# servo.net
KiCad netlist of a schematic drawn in EAGLE
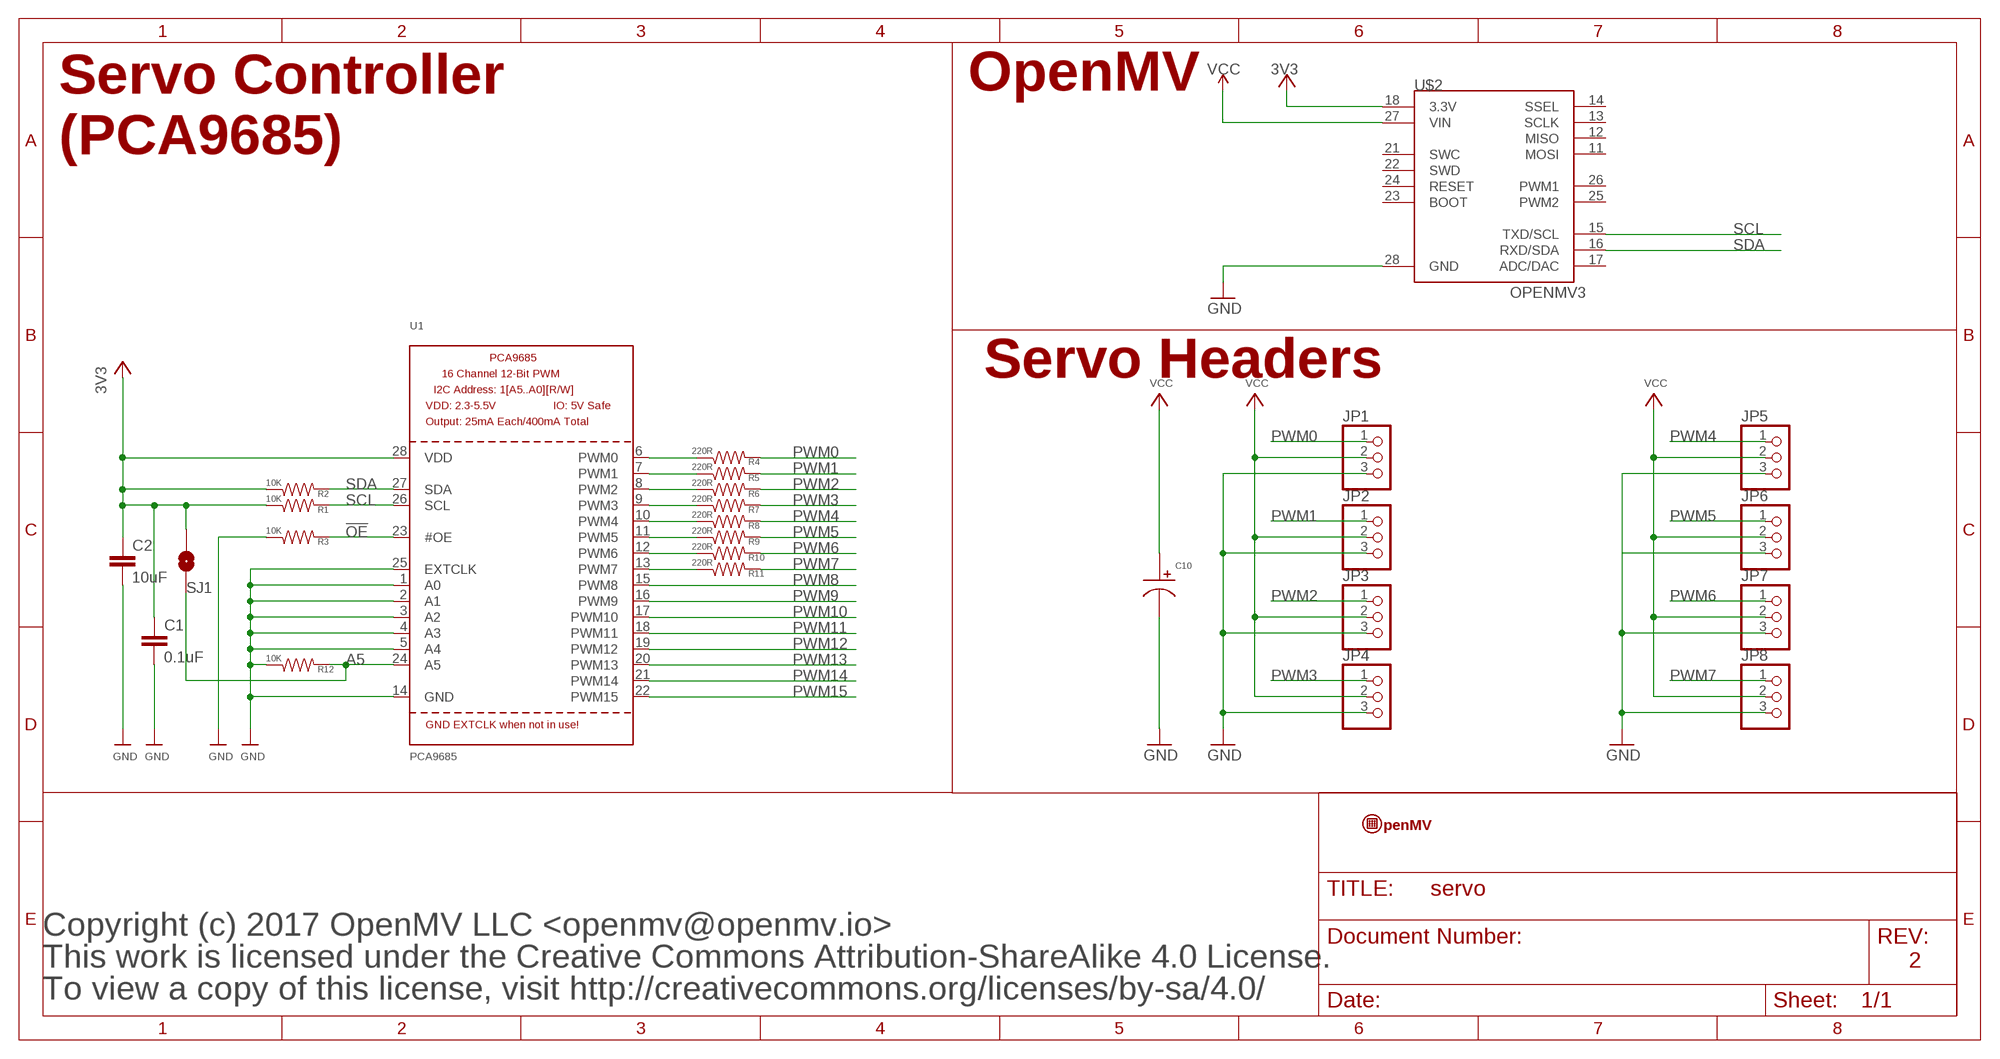
[diagram p0: schematic, sheet 1]

(export (version "E")
  (design (tool "Eeschema 10.0.6"))
  (components
    (comp (ref "C1")
      (value "0.1uF")
      (footprint "eagle-import:0603-CAP")
      (libsource (lib "eagle-import") (part "CAP0603-CAP"))
    )
    (comp (ref "C2")
      (value "10uF")
      (footprint "eagle-import:0805")
      (libsource (lib "eagle-import") (part "CAP0805"))
    )
    (comp (ref "C10")
      (value "CAPACITOR_P_10MM")
      (footprint "eagle-import:CP10MM")
      (libsource (lib "eagle-import") (part "CAPACITOR_P_10MM"))
    )
    (comp (ref "JP1")
      (value "PINHD-1X3")
      (footprint "eagle-import:1X03")
      (libsource (lib "eagle-import") (part "PINHD-1X3"))
    )
    (comp (ref "JP2")
      (value "PINHD-1X3")
      (footprint "eagle-import:1X03")
      (libsource (lib "eagle-import") (part "PINHD-1X3"))
    )
    (comp (ref "JP3")
      (value "PINHD-1X3")
      (footprint "eagle-import:1X03")
      (libsource (lib "eagle-import") (part "PINHD-1X3"))
    )
    (comp (ref "JP4")
      (value "PINHD-1X3")
      (footprint "eagle-import:1X03")
      (libsource (lib "eagle-import") (part "PINHD-1X3"))
    )
    (comp (ref "JP5")
      (value "PINHD-1X3")
      (footprint "eagle-import:1X03")
      (libsource (lib "eagle-import") (part "PINHD-1X3"))
    )
    (comp (ref "JP6")
      (value "PINHD-1X3")
      (footprint "eagle-import:1X03")
      (libsource (lib "eagle-import") (part "PINHD-1X3"))
    )
    (comp (ref "JP7")
      (value "PINHD-1X3")
      (footprint "eagle-import:1X03")
      (libsource (lib "eagle-import") (part "PINHD-1X3"))
    )
    (comp (ref "JP8")
      (value "PINHD-1X3")
      (footprint "eagle-import:1X03")
      (libsource (lib "eagle-import") (part "PINHD-1X3"))
    )
    (comp (ref "R1")
      (value "10K")
      (footprint "eagle-import:0603-RES")
      (libsource (lib "eagle-import") (part "RESISTOR0603-RES"))
    )
    (comp (ref "R2")
      (value "10K")
      (footprint "eagle-import:0603-RES")
      (libsource (lib "eagle-import") (part "RESISTOR0603-RES"))
    )
    (comp (ref "R3")
      (value "10K")
      (footprint "eagle-import:0603-RES")
      (libsource (lib "eagle-import") (part "RESISTOR0603-RES"))
    )
    (comp (ref "R4")
      (value "220R")
      (footprint "eagle-import:0603-RES")
      (libsource (lib "eagle-import") (part "RESISTOR0603-RES"))
    )
    (comp (ref "R5")
      (value "220R")
      (footprint "eagle-import:0603-RES")
      (libsource (lib "eagle-import") (part "RESISTOR0603-RES"))
    )
    (comp (ref "R6")
      (value "220R")
      (footprint "eagle-import:0603-RES")
      (libsource (lib "eagle-import") (part "RESISTOR0603-RES"))
    )
    (comp (ref "R7")
      (value "220R")
      (footprint "eagle-import:0603-RES")
      (libsource (lib "eagle-import") (part "RESISTOR0603-RES"))
    )
    (comp (ref "R8")
      (value "220R")
      (footprint "eagle-import:0603-RES")
      (libsource (lib "eagle-import") (part "RESISTOR0603-RES"))
    )
    (comp (ref "R9")
      (value "220R")
      (footprint "eagle-import:0603-RES")
      (libsource (lib "eagle-import") (part "RESISTOR0603-RES"))
    )
    (comp (ref "R10")
      (value "220R")
      (footprint "eagle-import:0603-RES")
      (libsource (lib "eagle-import") (part "RESISTOR0603-RES"))
    )
    (comp (ref "R11")
      (value "220R")
      (footprint "eagle-import:0603-RES")
      (libsource (lib "eagle-import") (part "RESISTOR0603-RES"))
    )
    (comp (ref "R12")
      (value "10K")
      (footprint "eagle-import:0603-RES")
      (libsource (lib "eagle-import") (part "RESISTOR0603-RES"))
    )
    (comp (ref "SJ1")
      (value "SOLDERJUMPERNO")
      (footprint "eagle-import:SJ_2S-NO")
      (libsource (lib "eagle-import") (part "SOLDERJUMPERNO"))
    )
    (comp (ref "U$2")
      (value "OPENMV3")
      (footprint "eagle-import:OPENMV3")
      (libsource (lib "eagle-import") (part "OPENMV3"))
    )
    (comp (ref "U$9")
      (value "OPENMV-LOGO")
      (footprint "eagle-import:OPENMV-LOGO")
      (libsource (lib "eagle-import") (part "OPENMV-LOGO"))
    )
    (comp (ref "U1")
      (value "PCA9685")
      (footprint "eagle-import:TSSOP28")
      (libsource (lib "eagle-import") (part "PCA9685"))
    )
  )
  (nets
    (net (code "1") (name "/A5") (class "Default")
      (node (ref "R12") (pin "2") (pinfunction "2_2") (pintype "passive"))
      (node (ref "SJ1") (pin "1") (pinfunction "1_1") (pintype "passive"))
      (node (ref "U1") (pin "24") (pinfunction "A5_24") (pintype "bidirectional"))
    )
    (net (code "2") (name "/PWM0") (class "Default")
      (node (ref "JP1") (pin "1") (pinfunction "1_1") (pintype "passive"))
      (node (ref "R4") (pin "2") (pinfunction "2_2") (pintype "passive"))
    )
    (net (code "3") (name "/PWM1") (class "Default")
      (node (ref "JP2") (pin "1") (pinfunction "1_1") (pintype "passive"))
      (node (ref "R5") (pin "2") (pinfunction "2_2") (pintype "passive"))
    )
    (net (code "4") (name "/PWM2") (class "Default")
      (node (ref "JP3") (pin "1") (pinfunction "1_1") (pintype "passive"))
      (node (ref "R6") (pin "2") (pinfunction "2_2") (pintype "passive"))
    )
    (net (code "5") (name "/PWM3") (class "Default")
      (node (ref "JP4") (pin "1") (pinfunction "1_1") (pintype "passive"))
      (node (ref "R7") (pin "2") (pinfunction "2_2") (pintype "passive"))
    )
    (net (code "6") (name "/PWM4") (class "Default")
      (node (ref "JP5") (pin "1") (pinfunction "1_1") (pintype "passive"))
      (node (ref "R8") (pin "2") (pinfunction "2_2") (pintype "passive"))
    )
    (net (code "7") (name "/PWM5") (class "Default")
      (node (ref "JP6") (pin "1") (pinfunction "1_1") (pintype "passive"))
      (node (ref "R9") (pin "2") (pinfunction "2_2") (pintype "passive"))
    )
    (net (code "8") (name "/PWM6") (class "Default")
      (node (ref "JP7") (pin "1") (pinfunction "1_1") (pintype "passive"))
      (node (ref "R10") (pin "2") (pinfunction "2_2") (pintype "passive"))
    )
    (net (code "9") (name "/PWM7") (class "Default")
      (node (ref "JP8") (pin "1") (pinfunction "1_1") (pintype "passive"))
      (node (ref "R11") (pin "2") (pinfunction "2_2") (pintype "passive"))
    )
    (net (code "10") (name "/PWM8") (class "Default")
      (node (ref "U1") (pin "15") (pinfunction "PWM8_15") (pintype "output"))
    )
    (net (code "11") (name "/PWM9") (class "Default")
      (node (ref "U1") (pin "16") (pinfunction "PWM9_16") (pintype "output"))
    )
    (net (code "12") (name "/PWM10") (class "Default")
      (node (ref "U1") (pin "17") (pinfunction "PWM10_17") (pintype "output"))
    )
    (net (code "13") (name "/PWM11") (class "Default")
      (node (ref "U1") (pin "18") (pinfunction "PWM11_18") (pintype "output"))
    )
    (net (code "14") (name "/PWM12") (class "Default")
      (node (ref "U1") (pin "19") (pinfunction "PWM12_19") (pintype "output"))
    )
    (net (code "15") (name "/PWM13") (class "Default")
      (node (ref "U1") (pin "20") (pinfunction "PWM13_20") (pintype "output"))
    )
    (net (code "16") (name "/PWM14") (class "Default")
      (node (ref "U1") (pin "21") (pinfunction "PWM14_21") (pintype "output"))
    )
    (net (code "17") (name "/PWM15") (class "Default")
      (node (ref "U1") (pin "22") (pinfunction "PWM15_22") (pintype "output"))
    )
    (net (code "18") (name "/SCL") (class "Default")
      (node (ref "R1") (pin "2") (pinfunction "2_2") (pintype "passive"))
      (node (ref "U$2") (pin "15") (pinfunction "TXD/SCL_15") (pintype "bidirectional"))
      (node (ref "U1") (pin "26") (pinfunction "SCL_26") (pintype "bidirectional"))
    )
    (net (code "19") (name "/SDA") (class "Default")
      (node (ref "R2") (pin "2") (pinfunction "2_2") (pintype "passive"))
      (node (ref "U$2") (pin "16") (pinfunction "RXD/SDA_16") (pintype "bidirectional"))
      (node (ref "U1") (pin "27") (pinfunction "SDA_27") (pintype "bidirectional"))
    )
    (net (code "20") (name "/~{OE}") (class "Default")
      (node (ref "R3") (pin "2") (pinfunction "2_2") (pintype "passive"))
      (node (ref "U1") (pin "23") (pinfunction "#OE_23") (pintype "input"))
    )
    (net (code "21") (name "3V3") (class "Default")
      (node (ref "C1") (pin "1") (pinfunction "1_1") (pintype "passive"))
      (node (ref "C2") (pin "1") (pinfunction "1_1") (pintype "passive"))
      (node (ref "R1") (pin "1") (pinfunction "1_1") (pintype "passive"))
      (node (ref "R2") (pin "1") (pinfunction "1_1") (pintype "passive"))
      (node (ref "SJ1") (pin "2") (pinfunction "2_2") (pintype "passive"))
      (node (ref "U$2") (pin "18") (pinfunction "3.3V_18") (pintype "power_in"))
      (node (ref "U1") (pin "28") (pinfunction "VDD_28") (pintype "power_in"))
    )
    (net (code "22") (name "GND") (class "Default")
      (node (ref "C1") (pin "2") (pinfunction "2_2") (pintype "passive"))
      (node (ref "C10") (pin "P$2") (pinfunction "P$2_P$2") (pintype "passive"))
      (node (ref "C2") (pin "2") (pinfunction "2_2") (pintype "passive"))
      (node (ref "JP1") (pin "3") (pinfunction "3_3") (pintype "passive"))
      (node (ref "JP2") (pin "3") (pinfunction "3_3") (pintype "passive"))
      (node (ref "JP3") (pin "3") (pinfunction "3_3") (pintype "passive"))
      (node (ref "JP4") (pin "3") (pinfunction "3_3") (pintype "passive"))
      (node (ref "JP5") (pin "3") (pinfunction "3_3") (pintype "passive"))
      (node (ref "JP6") (pin "3") (pinfunction "3_3") (pintype "passive"))
      (node (ref "JP7") (pin "3") (pinfunction "3_3") (pintype "passive"))
      (node (ref "JP8") (pin "3") (pinfunction "3_3") (pintype "passive"))
      (node (ref "R12") (pin "1") (pinfunction "1_1") (pintype "passive"))
      (node (ref "R3") (pin "1") (pinfunction "1_1") (pintype "passive"))
      (node (ref "U$2") (pin "28") (pinfunction "GND_28") (pintype "power_in"))
      (node (ref "U1") (pin "1") (pinfunction "A0_1") (pintype "bidirectional"))
      (node (ref "U1") (pin "14") (pinfunction "GND_14") (pintype "power_in"))
      (node (ref "U1") (pin "2") (pinfunction "A1_2") (pintype "bidirectional"))
      (node (ref "U1") (pin "25") (pinfunction "EXTCLK_25") (pintype "input"))
      (node (ref "U1") (pin "3") (pinfunction "A2_3") (pintype "bidirectional"))
      (node (ref "U1") (pin "4") (pinfunction "A3_4") (pintype "bidirectional"))
      (node (ref "U1") (pin "5") (pinfunction "A4_5") (pintype "bidirectional"))
    )
    (net (code "23") (name "Net-(U1-PWM0)") (class "Default")
      (node (ref "R4") (pin "1") (pinfunction "1_1") (pintype "passive"))
      (node (ref "U1") (pin "6") (pinfunction "PWM0_6") (pintype "output"))
    )
    (net (code "24") (name "Net-(U1-PWM1)") (class "Default")
      (node (ref "R5") (pin "1") (pinfunction "1_1") (pintype "passive"))
      (node (ref "U1") (pin "7") (pinfunction "PWM1_7") (pintype "output"))
    )
    (net (code "25") (name "Net-(U1-PWM2)") (class "Default")
      (node (ref "R6") (pin "1") (pinfunction "1_1") (pintype "passive"))
      (node (ref "U1") (pin "8") (pinfunction "PWM2_8") (pintype "output"))
    )
    (net (code "26") (name "Net-(U1-PWM3)") (class "Default")
      (node (ref "R7") (pin "1") (pinfunction "1_1") (pintype "passive"))
      (node (ref "U1") (pin "9") (pinfunction "PWM3_9") (pintype "output"))
    )
    (net (code "27") (name "Net-(U1-PWM4)") (class "Default")
      (node (ref "R8") (pin "1") (pinfunction "1_1") (pintype "passive"))
      (node (ref "U1") (pin "10") (pinfunction "PWM4_10") (pintype "output"))
    )
    (net (code "28") (name "Net-(U1-PWM5)") (class "Default")
      (node (ref "R9") (pin "1") (pinfunction "1_1") (pintype "passive"))
      (node (ref "U1") (pin "11") (pinfunction "PWM5_11") (pintype "output"))
    )
    (net (code "29") (name "Net-(U1-PWM6)") (class "Default")
      (node (ref "R10") (pin "1") (pinfunction "1_1") (pintype "passive"))
      (node (ref "U1") (pin "12") (pinfunction "PWM6_12") (pintype "output"))
    )
    (net (code "30") (name "Net-(U1-PWM7)") (class "Default")
      (node (ref "R11") (pin "1") (pinfunction "1_1") (pintype "passive"))
      (node (ref "U1") (pin "13") (pinfunction "PWM7_13") (pintype "output"))
    )
    (net (code "31") (name "VCC") (class "Default")
      (node (ref "C10") (pin "P$1") (pinfunction "P$1_P$1") (pintype "passive"))
      (node (ref "JP1") (pin "2") (pinfunction "2_2") (pintype "passive"))
      (node (ref "JP2") (pin "2") (pinfunction "2_2") (pintype "passive"))
      (node (ref "JP3") (pin "2") (pinfunction "2_2") (pintype "passive"))
      (node (ref "JP4") (pin "2") (pinfunction "2_2") (pintype "passive"))
      (node (ref "JP5") (pin "2") (pinfunction "2_2") (pintype "passive"))
      (node (ref "JP6") (pin "2") (pinfunction "2_2") (pintype "passive"))
      (node (ref "JP7") (pin "2") (pinfunction "2_2") (pintype "passive"))
      (node (ref "JP8") (pin "2") (pinfunction "2_2") (pintype "passive"))
      (node (ref "U$2") (pin "27") (pinfunction "VIN_27") (pintype "power_in"))
    )
    (net (code "32") (name "unconnected-(U$2-ADC{slash}DAC-Pad17)") (class "Default")
      (node (ref "U$2") (pin "17") (pinfunction "ADC/DAC_17") (pintype "bidirectional"))
    )
    (net (code "33") (name "unconnected-(U$2-BOOT-Pad23)") (class "Default")
      (node (ref "U$2") (pin "23") (pinfunction "BOOT_23") (pintype "bidirectional"))
    )
    (net (code "34") (name "unconnected-(U$2-MISO-Pad12)") (class "Default")
      (node (ref "U$2") (pin "12") (pinfunction "MISO_12") (pintype "bidirectional"))
    )
    (net (code "35") (name "unconnected-(U$2-MOSI-Pad11)") (class "Default")
      (node (ref "U$2") (pin "11") (pinfunction "MOSI_11") (pintype "bidirectional"))
    )
    (net (code "36") (name "unconnected-(U$2-PWM1-Pad26)") (class "Default")
      (node (ref "U$2") (pin "26") (pinfunction "PWM1_26") (pintype "bidirectional"))
    )
    (net (code "37") (name "unconnected-(U$2-PWM2-Pad25)") (class "Default")
      (node (ref "U$2") (pin "25") (pinfunction "PWM2_25") (pintype "bidirectional"))
    )
    (net (code "38") (name "unconnected-(U$2-RESET-Pad24)") (class "Default")
      (node (ref "U$2") (pin "24") (pinfunction "RESET_24") (pintype "bidirectional"))
    )
    (net (code "39") (name "unconnected-(U$2-SCLK-Pad13)") (class "Default")
      (node (ref "U$2") (pin "13") (pinfunction "SCLK_13") (pintype "bidirectional"))
    )
    (net (code "40") (name "unconnected-(U$2-SSEL-Pad14)") (class "Default")
      (node (ref "U$2") (pin "14") (pinfunction "SSEL_14") (pintype "bidirectional"))
    )
    (net (code "41") (name "unconnected-(U$2-SWC-Pad21)") (class "Default")
      (node (ref "U$2") (pin "21") (pinfunction "SWC_21") (pintype "bidirectional"))
    )
    (net (code "42") (name "unconnected-(U$2-SWD-Pad22)") (class "Default")
      (node (ref "U$2") (pin "22") (pinfunction "SWD_22") (pintype "bidirectional"))
    )
  )
)
